# LT4320.net
KiCad netlist of a schematic drawn in Altium Designer
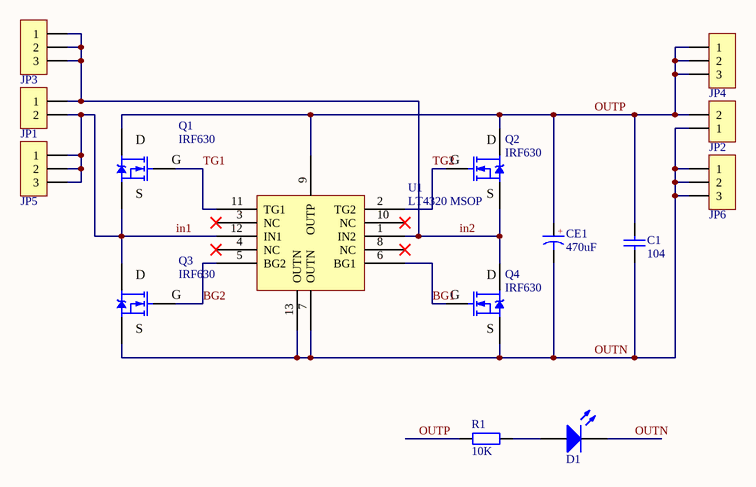
[diagram p0: LT4320同步整流.SchDoc]

(export (version "E")
  (design (tool "Eeschema 10.0.6"))
  (components
    (comp (ref "C1")
      (value "104")
      (footprint "MLCC5.08-A")
      (description "瓷片电容")
      (libsource (lib "0.1 - 电阻-电容-电感-磁珠-电位器") (part "CC"))
    )
    (comp (ref "CE1")
      (value "470uF")
      (footprint "CAP 5.0*12.5*20 - BK")
      (description "直插电解电容")
      (libsource (lib "0.1 - 电阻-电容-电感-磁珠-电位器") (part "CE"))
    )
    (comp (ref "D1")
      (value "LED")
      (footprint "LED 3MM-R")
      (description "发光二极管")
      (libsource (lib "0.3 - LED发光二极管") (part "LED"))
    )
    (comp (ref "JP1")
      (value "HDR-1X2")
      (footprint "KF301-5.0-2P")
      (description "2P接插件")
      (libsource (lib "5.5 - 接插件-脚距2.54 (100mil) ") (part "Header 2"))
    )
    (comp (ref "JP2")
      (value "HDR-1X2")
      (footprint "KF301-5.0-2P")
      (description "2P接插件")
      (libsource (lib "") (part "Header 2_1"))
    )
    (comp (ref "JP3")
      (value "HDR-1X3")
      (footprint "HDR2.54-LI-3P")
      (description "3P接插件")
      (libsource (lib "") (part "Header 3_1"))
    )
    (comp (ref "JP4")
      (value "HDR-1X3")
      (footprint "HDR2.54-LI-3P")
      (description "3P接插件")
      (libsource (lib "5.5 - 接插件-脚距2.54 (100mil) ") (part "Header 3"))
    )
    (comp (ref "JP5")
      (value "HDR-1X3")
      (footprint "HDR2.54-LI-3P")
      (description "3P接插件")
      (libsource (lib "") (part "Header 3_1"))
    )
    (comp (ref "JP6")
      (value "HDR-1X3")
      (footprint "HDR2.54-LI-3P")
      (description "3P接插件")
      (libsource (lib "5.5 - 接插件-脚距2.54 (100mil) ") (part "Header 3"))
    )
    (comp (ref "Q1")
      (value "IRF630")
      (footprint "TO220A")
      (description "N沟道 200V/9.2A")
      (libsource (lib "0.4 - 三极管-场效应管-可控硅") (part "IRF630"))
    )
    (comp (ref "Q2")
      (value "IRF630")
      (footprint "TO220A")
      (description "N沟道 200V/9.2A")
      (libsource (lib "0.4 - 三极管-场效应管-可控硅") (part "IRF630"))
    )
    (comp (ref "Q3")
      (value "IRF630")
      (footprint "TO220A")
      (description "N沟道 200V/9.2A")
      (libsource (lib "0.4 - 三极管-场效应管-可控硅") (part "IRF630"))
    )
    (comp (ref "Q4")
      (value "IRF630")
      (footprint "TO220A")
      (description "N沟道 200V/9.2A")
      (libsource (lib "0.4 - 三极管-场效应管-可控硅") (part "IRF630"))
    )
    (comp (ref "R1")
      (value "10K")
      (footprint "RS 1/4W")
      (description "色环电阻")
      (libsource (lib "0.1 - 电阻-电容-电感-磁珠-电位器") (part "R-S"))
    )
    (comp (ref "U1")
      (value "LT4320 MSOP")
      (footprint "MSOP-12EP")
      (description "LT4320 封装形式MSOP-12")
      (libsource (lib "1.1 - 电源类芯片") (part "LT4320 MSOP"))
    )
  )
  (nets
    (net (code "1") (name "/BG1") (class "Default")
      (node (ref "Q4") (pin "1") (pinfunction "G_1") (pintype "passive"))
      (node (ref "U1") (pin "6") (pinfunction "BG1_6") (pintype "passive"))
    )
    (net (code "2") (name "/BG2") (class "Default")
      (node (ref "Q3") (pin "1") (pinfunction "G_1") (pintype "passive"))
      (node (ref "U1") (pin "5") (pinfunction "BG2_5") (pintype "passive"))
    )
    (net (code "3") (name "/OUTN") (class "Default")
      (node (ref "C1") (pin "1") (pinfunction "1_1") (pintype "passive"))
      (node (ref "CE1") (pin "2") (pinfunction "2_2") (pintype "passive"))
      (node (ref "D1") (pin "2") (pinfunction "K_2") (pintype "passive"))
      (node (ref "JP2") (pin "1") (pinfunction "1_1") (pintype "passive"))
      (node (ref "JP6") (pin "1") (pinfunction "1_1") (pintype "passive"))
      (node (ref "JP6") (pin "2") (pinfunction "2_2") (pintype "passive"))
      (node (ref "JP6") (pin "3") (pinfunction "3_3") (pintype "passive"))
      (node (ref "Q3") (pin "3") (pinfunction "S_3") (pintype "passive"))
      (node (ref "Q4") (pin "3") (pinfunction "S_3") (pintype "passive"))
      (node (ref "U1") (pin "13") (pinfunction "OUTN_13") (pintype "passive"))
      (node (ref "U1") (pin "7") (pinfunction "OUTN_7") (pintype "passive"))
    )
    (net (code "4") (name "/OUTP") (class "Default")
      (node (ref "C1") (pin "2") (pinfunction "2_2") (pintype "passive"))
      (node (ref "CE1") (pin "1") (pinfunction "1_1") (pintype "passive"))
      (node (ref "JP2") (pin "2") (pinfunction "2_2") (pintype "passive"))
      (node (ref "JP4") (pin "1") (pinfunction "1_1") (pintype "passive"))
      (node (ref "JP4") (pin "2") (pinfunction "2_2") (pintype "passive"))
      (node (ref "JP4") (pin "3") (pinfunction "3_3") (pintype "passive"))
      (node (ref "Q1") (pin "2") (pinfunction "D_2") (pintype "passive"))
      (node (ref "Q2") (pin "2") (pinfunction "D_2") (pintype "passive"))
      (node (ref "R1") (pin "1") (pinfunction "1_1") (pintype "passive"))
      (node (ref "U1") (pin "9") (pinfunction "OUTP_9") (pintype "passive"))
    )
    (net (code "5") (name "/TG1") (class "Default")
      (node (ref "Q1") (pin "1") (pinfunction "G_1") (pintype "passive"))
      (node (ref "U1") (pin "11") (pinfunction "TG1_11") (pintype "passive"))
    )
    (net (code "6") (name "/TG2") (class "Default")
      (node (ref "Q2") (pin "1") (pinfunction "G_1") (pintype "passive"))
      (node (ref "U1") (pin "2") (pinfunction "TG2_2") (pintype "passive"))
    )
    (net (code "7") (name "/in1") (class "Default")
      (node (ref "JP1") (pin "2") (pinfunction "2_2") (pintype "passive"))
      (node (ref "JP5") (pin "1") (pinfunction "1_1") (pintype "passive"))
      (node (ref "JP5") (pin "2") (pinfunction "2_2") (pintype "passive"))
      (node (ref "JP5") (pin "3") (pinfunction "3_3") (pintype "passive"))
      (node (ref "Q1") (pin "3") (pinfunction "S_3") (pintype "passive"))
      (node (ref "Q3") (pin "2") (pinfunction "D_2") (pintype "passive"))
      (node (ref "U1") (pin "12") (pinfunction "IN1_12") (pintype "passive"))
    )
    (net (code "8") (name "/in2") (class "Default")
      (node (ref "JP1") (pin "1") (pinfunction "1_1") (pintype "passive"))
      (node (ref "JP3") (pin "1") (pinfunction "1_1") (pintype "passive"))
      (node (ref "JP3") (pin "2") (pinfunction "2_2") (pintype "passive"))
      (node (ref "JP3") (pin "3") (pinfunction "3_3") (pintype "passive"))
      (node (ref "Q2") (pin "3") (pinfunction "S_3") (pintype "passive"))
      (node (ref "Q4") (pin "2") (pinfunction "D_2") (pintype "passive"))
      (node (ref "U1") (pin "1") (pinfunction "IN2_1") (pintype "passive"))
    )
    (net (code "9") (name "Net-(D1-A)") (class "Default")
      (node (ref "D1") (pin "1") (pinfunction "A_1") (pintype "passive"))
      (node (ref "R1") (pin "2") (pinfunction "2_2") (pintype "passive"))
    )
    (net (code "10") (name "unconnected-(U1-NC-Pad3)") (class "Default")
      (node (ref "U1") (pin "3") (pinfunction "NC_3") (pintype "passive+no_connect"))
    )
    (net (code "11") (name "unconnected-(U1-NC-Pad4)") (class "Default")
      (node (ref "U1") (pin "4") (pinfunction "NC_4") (pintype "passive+no_connect"))
    )
    (net (code "12") (name "unconnected-(U1-NC-Pad8)") (class "Default")
      (node (ref "U1") (pin "8") (pinfunction "NC_8") (pintype "passive+no_connect"))
    )
    (net (code "13") (name "unconnected-(U1-NC-Pad10)") (class "Default")
      (node (ref "U1") (pin "10") (pinfunction "NC_10") (pintype "passive+no_connect"))
    )
  )
)
